# schematic.net
KiCad netlist of a schematic drawn in Altium Designer
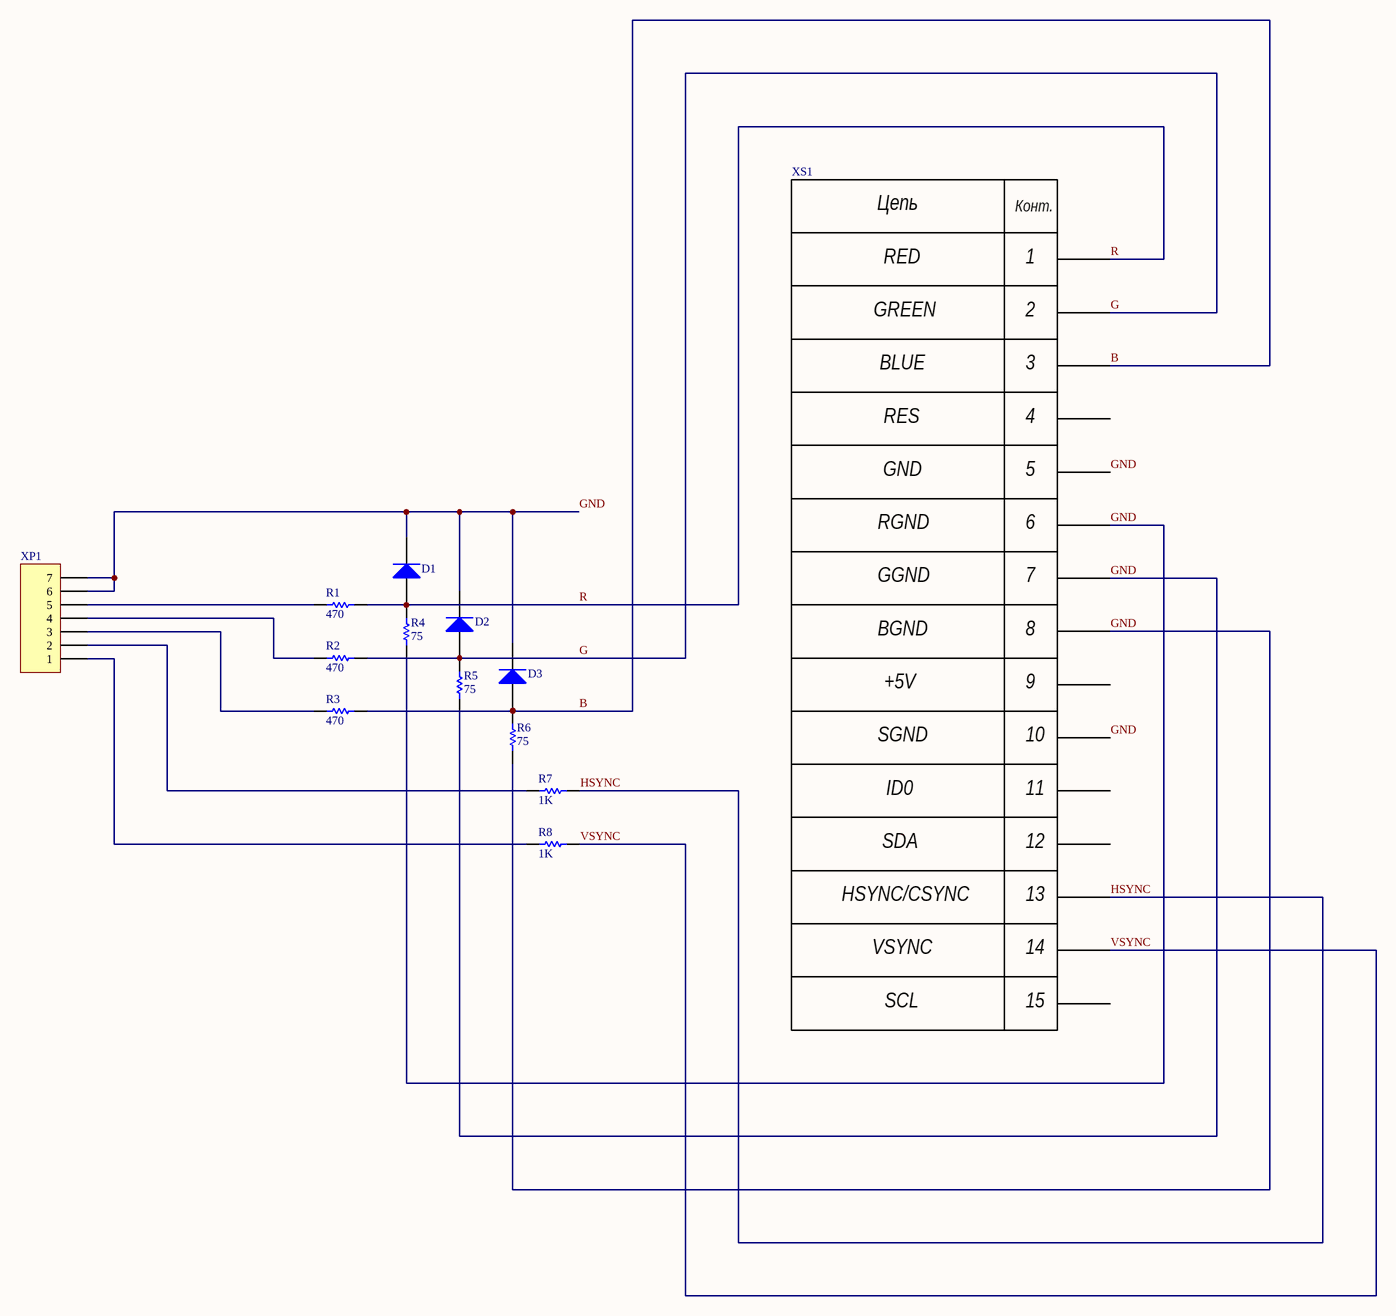
[diagram p0: schematic.SchDoc]

(export (version "E")
  (design (tool "Eeschema 10.0.6"))
  (components
    (comp (ref "D1")
      (value "Diode 1N4148")
      (footprint "DO-35")
      (description "High Conductance Fast Diode")
      (fields (field (name "PUBLISHER") "Altium Limited"))
      (libsource (lib "Miscellaneous Devices") (part "Diode 1N4148"))
    )
    (comp (ref "D2")
      (value "Diode 1N4148")
      (footprint "DO-35")
      (description "High Conductance Fast Diode")
      (fields (field (name "PUBLISHER") "Altium Limited"))
      (libsource (lib "Miscellaneous Devices") (part "Diode 1N4148"))
    )
    (comp (ref "D3")
      (value "Diode 1N4148")
      (footprint "DO-35")
      (description "High Conductance Fast Diode")
      (fields (field (name "PUBLISHER") "Altium Limited"))
      (libsource (lib "Miscellaneous Devices") (part "Diode 1N4148"))
    )
    (comp (ref "R1")
      (value "470")
      (footprint "AXIAL-0.3")
      (description "Resistor")
      (fields (field (name "PUBLISHER") "Altium Limited"))
      (libsource (lib "Miscellaneous Devices") (part "Res1"))
    )
    (comp (ref "R2")
      (value "470")
      (footprint "AXIAL-0.3")
      (description "Resistor")
      (fields (field (name "PUBLISHER") "Altium Limited"))
      (libsource (lib "Miscellaneous Devices") (part "Res1"))
    )
    (comp (ref "R3")
      (value "470")
      (footprint "AXIAL-0.3")
      (description "Resistor")
      (fields (field (name "PUBLISHER") "Altium Limited"))
      (libsource (lib "Miscellaneous Devices") (part "Res1"))
    )
    (comp (ref "R4")
      (value "75")
      (footprint "AXIAL-0.4")
      (description "Resistor")
      (fields (field (name "PUBLISHER") "Altium Limited"))
      (libsource (lib "Miscellaneous Devices") (part "Res1"))
    )
    (comp (ref "R5")
      (value "75")
      (footprint "AXIAL-0.4")
      (description "Resistor")
      (fields (field (name "PUBLISHER") "Altium Limited"))
      (libsource (lib "Miscellaneous Devices") (part "Res1"))
    )
    (comp (ref "R6")
      (value "75")
      (footprint "AXIAL-0.4")
      (description "Resistor")
      (fields (field (name "PUBLISHER") "Altium Limited"))
      (libsource (lib "Miscellaneous Devices") (part "Res1"))
    )
    (comp (ref "R7")
      (value "1K")
      (footprint "AXIAL-0.3")
      (description "Resistor")
      (fields (field (name "PUBLISHER") "Altium Limited"))
      (libsource (lib "Miscellaneous Devices") (part "Res1"))
    )
    (comp (ref "R8")
      (value "1K")
      (footprint "AXIAL-0.3")
      (description "Resistor")
      (fields (field (name "PUBLISHER") "Altium Limited"))
      (libsource (lib "Miscellaneous Devices") (part "Res1"))
    )
    (comp (ref "XP1")
      (value "Input Header")
      (footprint "HDR1X7")
      (description "Header, 7-Pin")
      (fields (field (name "PUBLISHER") "Altium Limited"))
      (libsource (lib "Miscellaneous Connectors") (part "Header 7"))
    )
    (comp (ref "XS1")
      (value "D-SUB VGA")
      (footprint "D-SUB VGA")
      (description "D-SUB VGA Female")
      (fields (field (name "PUBLISHER") "Victor Grigoryev"))
      (libsource (lib "Schlib1") (part "D-SUB VGA"))
    )
  )
  (nets
    (net (code "1") (name "/B") (class "Default")
      (node (ref "D3") (pin "1") (pinfunction "A_1") (pintype "passive"))
      (node (ref "R3") (pin "2") (pinfunction "2_2") (pintype "passive"))
      (node (ref "R6") (pin "1") (pinfunction "1_1") (pintype "passive"))
      (node (ref "XS1") (pin "3") (pintype "passive"))
    )
    (net (code "2") (name "/G") (class "Default")
      (node (ref "D2") (pin "1") (pinfunction "A_1") (pintype "passive"))
      (node (ref "R2") (pin "2") (pinfunction "2_2") (pintype "passive"))
      (node (ref "R5") (pin "1") (pinfunction "1_1") (pintype "passive"))
      (node (ref "XS1") (pin "2") (pintype "passive"))
    )
    (net (code "3") (name "/GND") (class "Default")
      (node (ref "D1") (pin "2") (pinfunction "K_2") (pintype "passive"))
      (node (ref "D2") (pin "2") (pinfunction "K_2") (pintype "passive"))
      (node (ref "D3") (pin "2") (pinfunction "K_2") (pintype "passive"))
      (node (ref "R4") (pin "2") (pinfunction "2_2") (pintype "passive"))
      (node (ref "R5") (pin "2") (pinfunction "2_2") (pintype "passive"))
      (node (ref "R6") (pin "2") (pinfunction "2_2") (pintype "passive"))
      (node (ref "XP1") (pin "6") (pinfunction "6_6") (pintype "passive"))
      (node (ref "XP1") (pin "7") (pinfunction "7_7") (pintype "passive"))
      (node (ref "XS1") (pin "10") (pintype "passive"))
      (node (ref "XS1") (pin "5") (pintype "passive"))
      (node (ref "XS1") (pin "6") (pintype "passive"))
      (node (ref "XS1") (pin "7") (pintype "passive"))
      (node (ref "XS1") (pin "8") (pintype "passive"))
    )
    (net (code "4") (name "/HSYNC") (class "Default")
      (node (ref "R7") (pin "1") (pinfunction "1_1") (pintype "passive"))
      (node (ref "XS1") (pin "13") (pintype "passive"))
    )
    (net (code "5") (name "/R") (class "Default")
      (node (ref "D1") (pin "1") (pinfunction "A_1") (pintype "passive"))
      (node (ref "R1") (pin "2") (pinfunction "2_2") (pintype "passive"))
      (node (ref "R4") (pin "1") (pinfunction "1_1") (pintype "passive"))
      (node (ref "XS1") (pin "1") (pintype "passive"))
    )
    (net (code "6") (name "/VSYNC") (class "Default")
      (node (ref "R8") (pin "1") (pinfunction "1_1") (pintype "passive"))
      (node (ref "XS1") (pin "14") (pintype "passive"))
    )
    (net (code "7") (name "Net-(R1-Pad1)") (class "Default")
      (node (ref "R1") (pin "1") (pinfunction "1_1") (pintype "passive"))
      (node (ref "XP1") (pin "5") (pinfunction "5_5") (pintype "passive"))
    )
    (net (code "8") (name "Net-(R2-Pad1)") (class "Default")
      (node (ref "R2") (pin "1") (pinfunction "1_1") (pintype "passive"))
      (node (ref "XP1") (pin "4") (pinfunction "4_4") (pintype "passive"))
    )
    (net (code "9") (name "Net-(R3-Pad1)") (class "Default")
      (node (ref "R3") (pin "1") (pinfunction "1_1") (pintype "passive"))
      (node (ref "XP1") (pin "3") (pinfunction "3_3") (pintype "passive"))
    )
    (net (code "10") (name "Net-(R7-Pad2)") (class "Default")
      (node (ref "R7") (pin "2") (pinfunction "2_2") (pintype "passive"))
      (node (ref "XP1") (pin "2") (pinfunction "2_2") (pintype "passive"))
    )
    (net (code "11") (name "Net-(R8-Pad2)") (class "Default")
      (node (ref "R8") (pin "2") (pinfunction "2_2") (pintype "passive"))
      (node (ref "XP1") (pin "1") (pinfunction "1_1") (pintype "passive"))
    )
    (net (code "12") (name "unconnected-(XS1-Pad4)") (class "Default")
      (node (ref "XS1") (pin "4") (pintype "passive"))
    )
    (net (code "13") (name "unconnected-(XS1-Pad9)") (class "Default")
      (node (ref "XS1") (pin "9") (pintype "passive"))
    )
    (net (code "14") (name "unconnected-(XS1-Pad11)") (class "Default")
      (node (ref "XS1") (pin "11") (pintype "passive"))
    )
    (net (code "15") (name "unconnected-(XS1-Pad12)") (class "Default")
      (node (ref "XS1") (pin "12") (pintype "passive"))
    )
    (net (code "16") (name "unconnected-(XS1-Pad15)") (class "Default")
      (node (ref "XS1") (pin "15") (pintype "passive"))
    )
  )
)
